# mp28164-buck-boost-flashlight-driver-tes.net
KiCad netlist of a schematic drawn in EAGLE
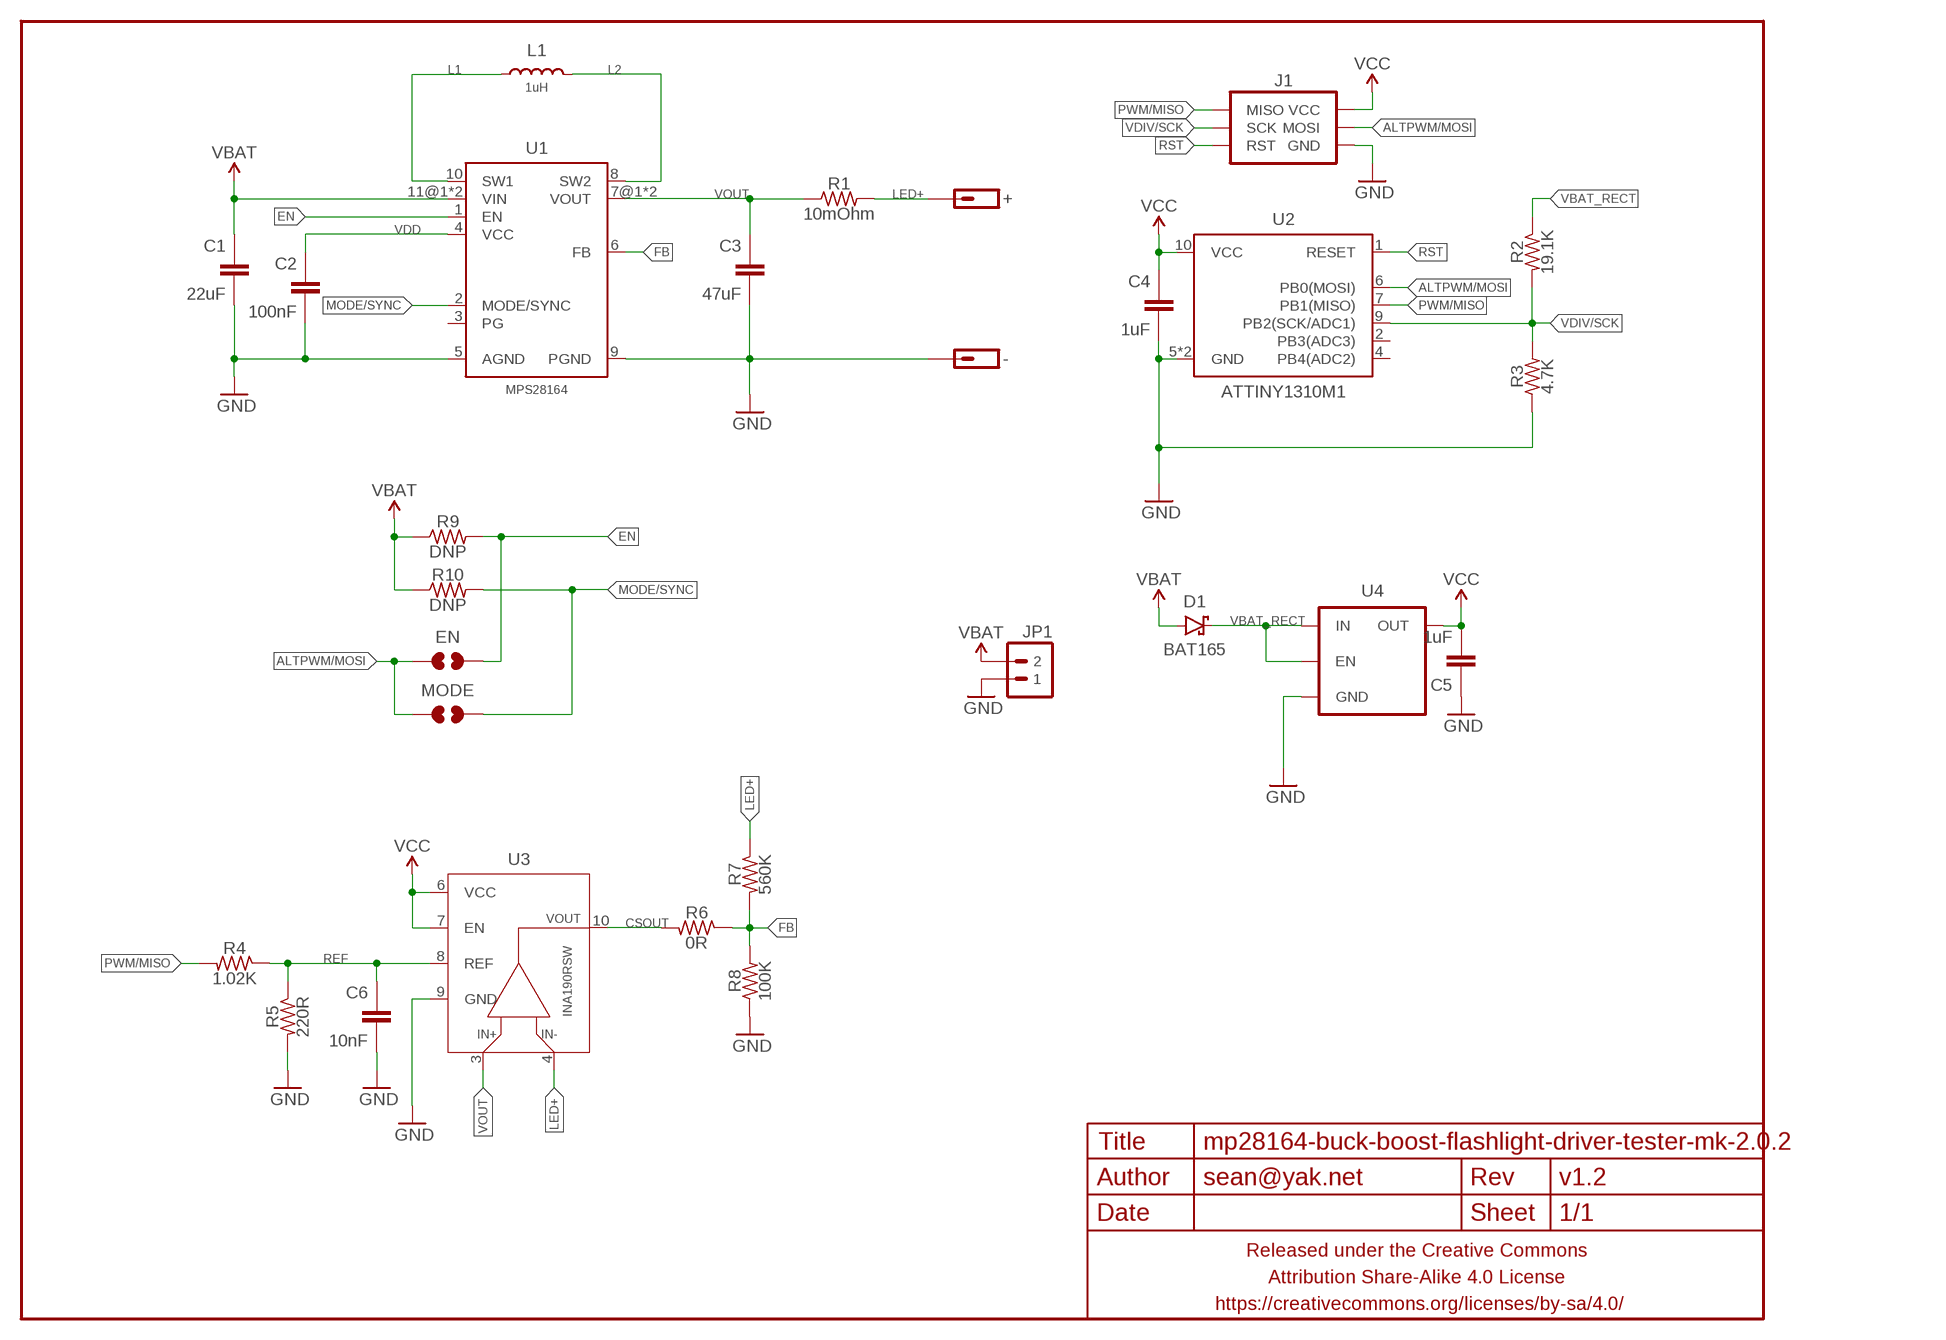
[diagram p0: schematic, sheet 1]

(export (version "E")
  (design (tool "Eeschema 10.0.6"))
  (components
    (comp (ref "+")
      (value "M01PTH-1.2MM-NS")
      (footprint "eagle-import:1X01-1.2MM-NS")
      (libsource (lib "eagle-import") (part "M01PTH-1.2MM-NS"))
    )
    (comp (ref "-")
      (value "M01PTH-1.2MM-NS")
      (footprint "eagle-import:1X01-1.2MM-NS")
      (libsource (lib "eagle-import") (part "M01PTH-1.2MM-NS"))
    )
    (comp (ref "C1")
      (value "22uF")
      (footprint "eagle-import:C1206")
      (libsource (lib "eagle-import") (part "CAPACITOR-CERAMICC1206"))
    )
    (comp (ref "C2")
      (value "100nF")
      (footprint "eagle-import:C0402")
      (libsource (lib "eagle-import") (part "CAPACITOR-CERAMICC0402"))
    )
    (comp (ref "C3")
      (value "47uF")
      (footprint "eagle-import:C1206")
      (libsource (lib "eagle-import") (part "CAPACITOR-CERAMICC1206"))
    )
    (comp (ref "C4")
      (value "1uF")
      (footprint "eagle-import:C0402")
      (libsource (lib "eagle-import") (part "CAPACITOR-CERAMICC0402"))
    )
    (comp (ref "C5")
      (value "1uF")
      (footprint "eagle-import:C0402")
      (libsource (lib "eagle-import") (part "CAPACITOR-CERAMICC0402"))
    )
    (comp (ref "C6")
      (value "10nF")
      (footprint "eagle-import:C0402")
      (libsource (lib "eagle-import") (part "CAPACITOR-CERAMICC0402"))
    )
    (comp (ref "D1")
      (value "BAT165")
      (footprint "eagle-import:SOD323-SCHOTTKY")
      (libsource (lib "eagle-import") (part "DIODE-SCHOTTKYSOD323"))
    )
    (comp (ref "EN")
      (value "JUMPER-PAD-2-NOYES_SILK")
      (footprint "eagle-import:PAD-JUMPER-2-NO_YES_SILK")
      (libsource (lib "eagle-import") (part "JUMPER-PAD-2-NOYES_SILK"))
    )
    (comp (ref "FRAME1")
      (value "FRAME-LETTERNO_PACKAGE")
      (footprint "eagle-import:DUMMY")
      (fields
        (field (name "DESIGNER") "sean@yak.net")
        (field (name "VERSION") "v1.2")
        (field (name "DESIGNER_1") "sean@yak.net")
        (field (name "VERSION_1") "v1.2")
      )
      (libsource (lib "eagle-import") (part "FRAME-LETTERNO_PACKAGE"))
    )
    (comp (ref "J1")
      (value "AVR_SPI_PRG_6PTH")
      (footprint "eagle-import:2X3")
      (libsource (lib "eagle-import") (part "AVR_SPI_PRG_6PTH"))
    )
    (comp (ref "JP1")
      (value "M02PTH-CENTERED")
      (footprint "eagle-import:1X02-CENTER")
      (libsource (lib "eagle-import") (part "M02PTH-CENTERED"))
    )
    (comp (ref "L1")
      (value "1uH")
      (footprint "eagle-import:XAL60XX")
      (libsource (lib "eagle-import") (part "INDUCTORXAL60XX"))
    )
    (comp (ref "MODE")
      (value "JUMPER-PAD-2-NOYES_SILK")
      (footprint "eagle-import:PAD-JUMPER-2-NO_YES_SILK")
      (libsource (lib "eagle-import") (part "JUMPER-PAD-2-NOYES_SILK"))
    )
    (comp (ref "R1")
      (value "10mOhm")
      (footprint "eagle-import:R1206")
      (libsource (lib "eagle-import") (part "RESISTORR1206"))
    )
    (comp (ref "R2")
      (value "19.1K")
      (footprint "eagle-import:R0402")
      (libsource (lib "eagle-import") (part "RESISTORR0402"))
    )
    (comp (ref "R3")
      (value "4.7K")
      (footprint "eagle-import:R0402")
      (libsource (lib "eagle-import") (part "RESISTORR0402"))
    )
    (comp (ref "R4")
      (value "1.02K")
      (footprint "eagle-import:R0402")
      (libsource (lib "eagle-import") (part "RESISTORR0402"))
    )
    (comp (ref "R5")
      (value "220R")
      (footprint "eagle-import:R0402")
      (libsource (lib "eagle-import") (part "RESISTORR0402"))
    )
    (comp (ref "R6")
      (value "0R")
      (footprint "eagle-import:R0402")
      (libsource (lib "eagle-import") (part "RESISTORR0402"))
    )
    (comp (ref "R7")
      (value "560K")
      (footprint "eagle-import:R0402")
      (libsource (lib "eagle-import") (part "RESISTORR0402"))
    )
    (comp (ref "R8")
      (value "100K")
      (footprint "eagle-import:R0402")
      (libsource (lib "eagle-import") (part "RESISTORR0402"))
    )
    (comp (ref "R9")
      (value "DNP")
      (footprint "eagle-import:R0402")
      (libsource (lib "eagle-import") (part "RESISTORR0402"))
    )
    (comp (ref "R10")
      (value "DNP")
      (footprint "eagle-import:R0402")
      (libsource (lib "eagle-import") (part "RESISTORR0402"))
    )
    (comp (ref "U1")
      (value "MPS28164")
      (footprint "eagle-import:MPS28164")
      (libsource (lib "eagle-import") (part "MPS28164"))
    )
    (comp (ref "U2")
      (value "ATTINY1310M1")
      (footprint "eagle-import:QFN10(2X5)")
      (libsource (lib "eagle-import") (part "ATTINY1310M1"))
    )
    (comp (ref "U3")
      (value "INA190RSW")
      (footprint "eagle-import:UQFN-10")
      (libsource (lib "eagle-import") (part "INA190RSW"))
    )
    (comp (ref "U4")
      (value "TLV30028DCK")
      (footprint "eagle-import:SC70")
      (libsource (lib "eagle-import") (part "V_REG_ENTLV700XXDCR"))
    )
  )
  (nets
    (net (code "1") (name "/CSOUT") (class "Default")
      (node (ref "R6") (pin "2") (pinfunction "2_2") (pintype "passive"))
      (node (ref "U3") (pin "10") (pinfunction "OUT_10") (pintype "bidirectional"))
    )
    (net (code "2") (name "/L1") (class "Default")
      (node (ref "L1") (pin "P$1") (pinfunction "1_P$1") (pintype "passive"))
      (node (ref "U1") (pin "10") (pinfunction "SW1_10") (pintype "bidirectional"))
    )
    (net (code "3") (name "/L2") (class "Default")
      (node (ref "L1") (pin "P$2") (pinfunction "2_P$2") (pintype "passive"))
      (node (ref "U1") (pin "8") (pinfunction "SW2_8") (pintype "bidirectional"))
    )
    (net (code "4") (name "/REF") (class "Default")
      (node (ref "C6") (pin "1") (pinfunction "1_1") (pintype "passive"))
      (node (ref "R4") (pin "1") (pinfunction "1_1") (pintype "passive"))
      (node (ref "R5") (pin "1") (pinfunction "1_1") (pintype "passive"))
      (node (ref "U3") (pin "8") (pinfunction "REF_8") (pintype "bidirectional"))
    )
    (net (code "5") (name "/VDD") (class "Default")
      (node (ref "C2") (pin "1") (pinfunction "1_1") (pintype "passive"))
      (node (ref "U1") (pin "4") (pinfunction "VCC_4") (pintype "bidirectional"))
    )
    (net (code "6") (name "ALTPWM{slash}MOSI") (class "Default")
      (node (ref "EN") (pin "1") (pinfunction "1_1") (pintype "passive"))
      (node (ref "J1") (pin "4") (pinfunction "MOSI_4") (pintype "passive"))
      (node (ref "MODE") (pin "1") (pinfunction "1_1") (pintype "passive"))
      (node (ref "U2") (pin "6") (pinfunction "PB0(MOSI)_6") (pintype "bidirectional"))
    )
    (net (code "7") (name "EN") (class "Default")
      (node (ref "EN") (pin "2") (pinfunction "2_2") (pintype "passive"))
      (node (ref "R9") (pin "2") (pinfunction "2_2") (pintype "passive"))
      (node (ref "U1") (pin "1") (pinfunction "EN_1") (pintype "bidirectional"))
    )
    (net (code "8") (name "FB") (class "Default")
      (node (ref "R6") (pin "1") (pinfunction "1_1") (pintype "passive"))
      (node (ref "R7") (pin "2") (pinfunction "2_2") (pintype "passive"))
      (node (ref "R8") (pin "2") (pinfunction "2_2") (pintype "passive"))
      (node (ref "U1") (pin "6") (pinfunction "FB_6") (pintype "bidirectional"))
    )
    (net (code "9") (name "GND") (class "Default")
      (node (ref "-") (pin "P$1") (pinfunction "1_P$1") (pintype "passive"))
      (node (ref "C1") (pin "2") (pinfunction "2_2") (pintype "passive"))
      (node (ref "C2") (pin "2") (pinfunction "2_2") (pintype "passive"))
      (node (ref "C3") (pin "2") (pinfunction "2_2") (pintype "passive"))
      (node (ref "C4") (pin "2") (pinfunction "2_2") (pintype "passive"))
      (node (ref "C5") (pin "1") (pinfunction "1_1") (pintype "passive"))
      (node (ref "C6") (pin "2") (pinfunction "2_2") (pintype "passive"))
      (node (ref "J1") (pin "6") (pinfunction "GND_6") (pintype "passive"))
      (node (ref "JP1") (pin "1") (pinfunction "1_1") (pintype "passive"))
      (node (ref "R3") (pin "1") (pinfunction "1_1") (pintype "passive"))
      (node (ref "R5") (pin "2") (pinfunction "2_2") (pintype "passive"))
      (node (ref "R8") (pin "1") (pinfunction "1_1") (pintype "passive"))
      (node (ref "U1") (pin "5") (pinfunction "AGND_5") (pintype "bidirectional"))
      (node (ref "U1") (pin "9") (pinfunction "PGND_9") (pintype "bidirectional"))
      (node (ref "U2") (pin "5") (pinfunction "GND_5") (pintype "bidirectional"))
      (node (ref "U2") (pin "PAD") (pinfunction "GND_PAD") (pintype "bidirectional"))
      (node (ref "U3") (pin "9") (pinfunction "GND_9") (pintype "bidirectional"))
      (node (ref "U4") (pin "2") (pinfunction "GND_2") (pintype "input"))
    )
    (net (code "10") (name "LED+") (class "Default")
      (node (ref "+") (pin "P$1") (pinfunction "1_P$1") (pintype "passive"))
      (node (ref "R1") (pin "2") (pinfunction "2_2") (pintype "passive"))
      (node (ref "R7") (pin "1") (pinfunction "1_1") (pintype "passive"))
      (node (ref "U3") (pin "4") (pinfunction "VIN-_4") (pintype "bidirectional"))
    )
    (net (code "11") (name "MODE{slash}SYNC") (class "Default")
      (node (ref "MODE") (pin "2") (pinfunction "2_2") (pintype "passive"))
      (node (ref "R10") (pin "2") (pinfunction "2_2") (pintype "passive"))
      (node (ref "U1") (pin "2") (pinfunction "MODE/SYNC_2") (pintype "bidirectional"))
    )
    (net (code "12") (name "PWM{slash}MISO") (class "Default")
      (node (ref "J1") (pin "1") (pinfunction "MISO_1") (pintype "passive"))
      (node (ref "R4") (pin "2") (pinfunction "2_2") (pintype "passive"))
      (node (ref "U2") (pin "7") (pinfunction "PB1(MISO)_7") (pintype "bidirectional"))
    )
    (net (code "13") (name "RST") (class "Default")
      (node (ref "J1") (pin "5") (pinfunction "RST_5") (pintype "passive"))
      (node (ref "U2") (pin "1") (pinfunction "RESET_1") (pintype "bidirectional"))
    )
    (net (code "14") (name "VBAT") (class "Default")
      (node (ref "C1") (pin "1") (pinfunction "1_1") (pintype "passive"))
      (node (ref "D1") (pin "A") (pinfunction "A_A") (pintype "passive"))
      (node (ref "JP1") (pin "2") (pinfunction "2_2") (pintype "passive"))
      (node (ref "R10") (pin "1") (pinfunction "1_1") (pintype "passive"))
      (node (ref "R9") (pin "1") (pinfunction "1_1") (pintype "passive"))
      (node (ref "U1") (pin "11@1") (pinfunction "VIN_11@1") (pintype "bidirectional"))
      (node (ref "U1") (pin "11@2") (pinfunction "VIN_11@2") (pintype "bidirectional"))
    )
    (net (code "15") (name "VBAT_RECT") (class "Default")
      (node (ref "D1") (pin "C") (pinfunction "C_C") (pintype "passive"))
      (node (ref "R2") (pin "1") (pinfunction "1_1") (pintype "passive"))
      (node (ref "U4") (pin "1") (pinfunction "IN_1") (pintype "input"))
      (node (ref "U4") (pin "3") (pinfunction "EN_3") (pintype "input"))
    )
    (net (code "16") (name "VCC") (class "Default")
      (node (ref "C4") (pin "1") (pinfunction "1_1") (pintype "passive"))
      (node (ref "C5") (pin "2") (pinfunction "2_2") (pintype "passive"))
      (node (ref "J1") (pin "2") (pinfunction "VCC_2") (pintype "passive"))
      (node (ref "U2") (pin "10") (pinfunction "VCC_10") (pintype "bidirectional"))
      (node (ref "U3") (pin "6") (pinfunction "VCC_6") (pintype "bidirectional"))
      (node (ref "U3") (pin "7") (pinfunction "EN_7") (pintype "bidirectional"))
      (node (ref "U4") (pin "5") (pinfunction "OUT_5") (pintype "passive"))
    )
    (net (code "17") (name "VDIV{slash}SCK") (class "Default")
      (node (ref "J1") (pin "3") (pinfunction "SCK_3") (pintype "passive"))
      (node (ref "R2") (pin "2") (pinfunction "2_2") (pintype "passive"))
      (node (ref "R3") (pin "2") (pinfunction "2_2") (pintype "passive"))
      (node (ref "U2") (pin "9") (pinfunction "PB2(SCK/ADC1)_9") (pintype "bidirectional"))
    )
    (net (code "18") (name "VOUT") (class "Default")
      (node (ref "C3") (pin "1") (pinfunction "1_1") (pintype "passive"))
      (node (ref "R1") (pin "1") (pinfunction "1_1") (pintype "passive"))
      (node (ref "U1") (pin "7@1") (pinfunction "VOUT_7@1") (pintype "bidirectional"))
      (node (ref "U1") (pin "7@2") (pinfunction "VOUT_7@2") (pintype "bidirectional"))
      (node (ref "U3") (pin "3") (pinfunction "VIN+_3") (pintype "bidirectional"))
    )
    (net (code "19") (name "unconnected-(U1-PG-Pad3)") (class "Default")
      (node (ref "U1") (pin "3") (pinfunction "PG_3") (pintype "bidirectional"))
    )
    (net (code "20") (name "unconnected-(U2-PB3(ADC3)-Pad2)") (class "Default")
      (node (ref "U2") (pin "2") (pinfunction "PB3(ADC3)_2") (pintype "bidirectional"))
    )
    (net (code "21") (name "unconnected-(U2-PB4(ADC2)-Pad4)") (class "Default")
      (node (ref "U2") (pin "4") (pinfunction "PB4(ADC2)_4") (pintype "bidirectional"))
    )
  )
)
